# shield1.net
KiCad netlist of a schematic drawn in EAGLE
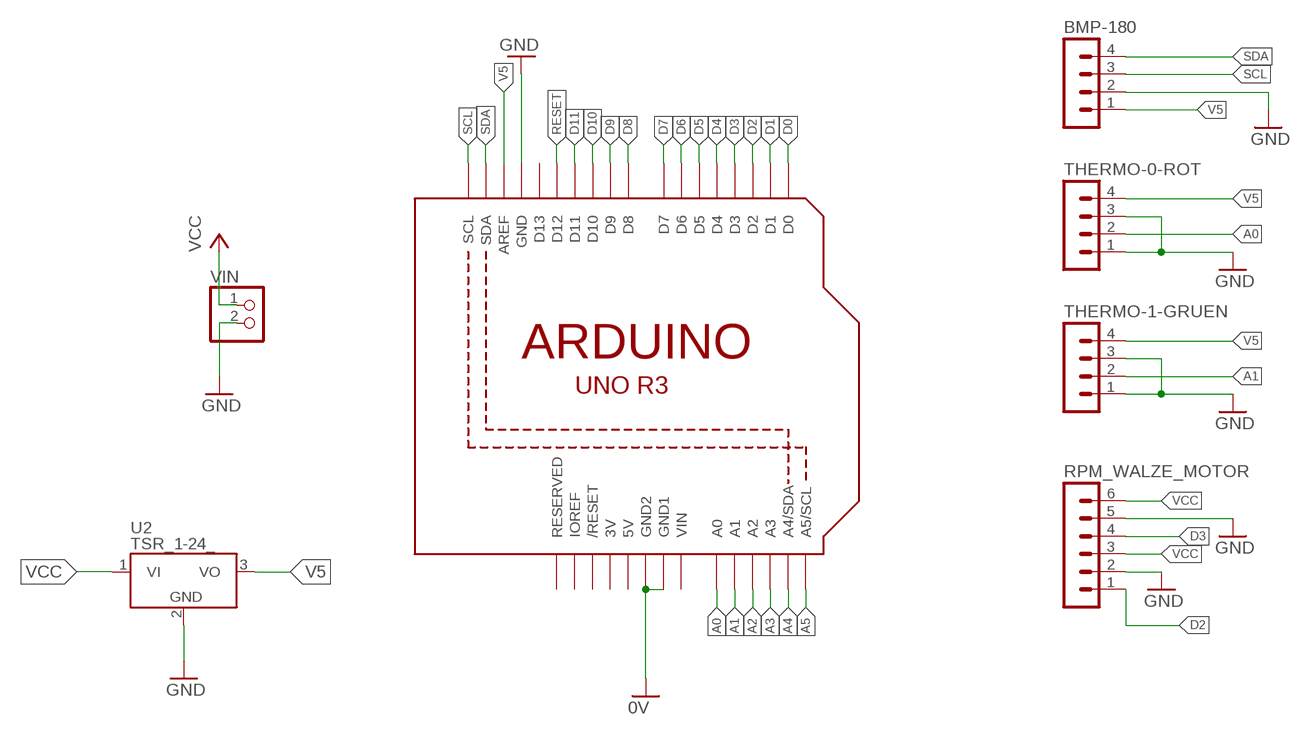
[diagram p0: schematic, sheet 1]

(export (version "E")
  (design (tool "Eeschema 10.0.6"))
  (components
    (comp (ref "BMP-180")
      (value "MA04-1")
      (footprint "eagle-import:MA04-1")
      (libsource (lib "eagle-import") (part "MA04-1"))
    )
    (comp (ref "RPM_WALZE_MOTOR")
      (value "MA06-1")
      (footprint "eagle-import:MA06-1")
      (libsource (lib "eagle-import") (part "MA06-1"))
    )
    (comp (ref "THERMO-0-ROT")
      (value "MA04-1")
      (footprint "eagle-import:MA04-1")
      (libsource (lib "eagle-import") (part "MA04-1"))
    )
    (comp (ref "THERMO-1-GRUEN")
      (value "MA04-1")
      (footprint "eagle-import:MA04-1")
      (libsource (lib "eagle-import") (part "MA04-1"))
    )
    (comp (ref "U1")
      (value "ARDUINOR3-BPLACE")
      (footprint "eagle-import:ARDUINOR3-BPLACE")
      (libsource (lib "eagle-import") (part "ARDUINOR3-BPLACE"))
    )
    (comp (ref "U2")
      (value "TSR_1-24_")
      (footprint "eagle-import:TSR-1")
      (libsource (lib "eagle-import") (part "TSR_1-24_"))
    )
    (comp (ref "VIN")
      (value "PINHD-1X2")
      (footprint "eagle-import:1X02")
      (libsource (lib "eagle-import") (part "PINHD-1X2"))
    )
  )
  (nets
    (net (code "1") (name "/3V") (class "Default")
      (node (ref "U1") (pin "3V") (pinfunction "3V_3V") (pintype "power_in"))
    )
    (net (code "2") (name "/5V") (class "Default")
      (node (ref "U1") (pin "5V") (pinfunction "5V_5V") (pintype "power_in"))
    )
    (net (code "3") (name "/VIN") (class "Default")
      (node (ref "U1") (pin "VIN") (pinfunction "VIN_VIN") (pintype "power_in"))
    )
    (net (code "4") (name "0V") (class "Default")
      (node (ref "BMP-180") (pin "2") (pinfunction "2_2") (pintype "passive"))
      (node (ref "RPM_WALZE_MOTOR") (pin "2") (pinfunction "2_2") (pintype "passive"))
      (node (ref "RPM_WALZE_MOTOR") (pin "5") (pinfunction "5_5") (pintype "passive"))
      (node (ref "THERMO-0-ROT") (pin "1") (pinfunction "1_1") (pintype "passive"))
      (node (ref "THERMO-0-ROT") (pin "3") (pinfunction "3_3") (pintype "passive"))
      (node (ref "THERMO-1-GRUEN") (pin "1") (pinfunction "1_1") (pintype "passive"))
      (node (ref "THERMO-1-GRUEN") (pin "3") (pinfunction "3_3") (pintype "passive"))
      (node (ref "U1") (pin "GND") (pinfunction "GND_GND") (pintype "power_in"))
      (node (ref "U1") (pin "GND1") (pinfunction "GND1_GND1") (pintype "power_in"))
      (node (ref "U1") (pin "GND2") (pinfunction "GND2_GND2") (pintype "power_in"))
      (node (ref "U2") (pin "2") (pinfunction "GND_2") (pintype "power_in"))
      (node (ref "VIN") (pin "2") (pinfunction "2_2") (pintype "passive"))
    )
    (net (code "5") (name "A0") (class "Default")
      (node (ref "THERMO-0-ROT") (pin "2") (pinfunction "2_2") (pintype "passive"))
      (node (ref "U1") (pin "A0") (pinfunction "A0_A0") (pintype "bidirectional"))
    )
    (net (code "6") (name "A1") (class "Default")
      (node (ref "THERMO-1-GRUEN") (pin "2") (pinfunction "2_2") (pintype "passive"))
      (node (ref "U1") (pin "A1") (pinfunction "A1_A1") (pintype "bidirectional"))
    )
    (net (code "7") (name "A2") (class "Default")
      (node (ref "U1") (pin "A2") (pinfunction "A2_A2") (pintype "bidirectional"))
    )
    (net (code "8") (name "A3") (class "Default")
      (node (ref "U1") (pin "A3") (pinfunction "A3_A3") (pintype "bidirectional"))
    )
    (net (code "9") (name "A4") (class "Default")
      (node (ref "U1") (pin "A4") (pinfunction "A4/SDA_A4") (pintype "bidirectional"))
    )
    (net (code "10") (name "A5") (class "Default")
      (node (ref "U1") (pin "A5") (pinfunction "A5/SCL_A5") (pintype "bidirectional"))
    )
    (net (code "11") (name "D0") (class "Default")
      (node (ref "U1") (pin "D0") (pinfunction "D0_D0") (pintype "bidirectional"))
    )
    (net (code "12") (name "D1") (class "Default")
      (node (ref "U1") (pin "D1") (pinfunction "D1_D1") (pintype "bidirectional"))
    )
    (net (code "13") (name "D2") (class "Default")
      (node (ref "RPM_WALZE_MOTOR") (pin "1") (pinfunction "1_1") (pintype "passive"))
      (node (ref "U1") (pin "D2") (pinfunction "D2_D2") (pintype "bidirectional"))
    )
    (net (code "14") (name "D3") (class "Default")
      (node (ref "RPM_WALZE_MOTOR") (pin "4") (pinfunction "4_4") (pintype "passive"))
      (node (ref "U1") (pin "D3") (pinfunction "D3_D3") (pintype "bidirectional"))
    )
    (net (code "15") (name "D4") (class "Default")
      (node (ref "U1") (pin "D4") (pinfunction "D4_D4") (pintype "bidirectional"))
    )
    (net (code "16") (name "D5") (class "Default")
      (node (ref "U1") (pin "D5") (pinfunction "D5_D5") (pintype "bidirectional"))
    )
    (net (code "17") (name "D6") (class "Default")
      (node (ref "U1") (pin "D6") (pinfunction "D6_D6") (pintype "bidirectional"))
    )
    (net (code "18") (name "D7") (class "Default")
      (node (ref "U1") (pin "D7") (pinfunction "D7_D7") (pintype "bidirectional"))
    )
    (net (code "19") (name "D8") (class "Default")
      (node (ref "U1") (pin "D8") (pinfunction "D8_D8") (pintype "bidirectional"))
    )
    (net (code "20") (name "D9") (class "Default")
      (node (ref "U1") (pin "D9") (pinfunction "D9_D9") (pintype "bidirectional"))
    )
    (net (code "21") (name "D10") (class "Default")
      (node (ref "U1") (pin "D10") (pinfunction "D10_D10") (pintype "bidirectional"))
    )
    (net (code "22") (name "D11") (class "Default")
      (node (ref "U1") (pin "D11") (pinfunction "D11_D11") (pintype "bidirectional"))
    )
    (net (code "23") (name "RESET") (class "Default")
      (node (ref "U1") (pin "D12") (pinfunction "D12_D12") (pintype "bidirectional"))
    )
    (net (code "24") (name "SCL") (class "Default")
      (node (ref "BMP-180") (pin "3") (pinfunction "3_3") (pintype "passive"))
      (node (ref "U1") (pin "SCL") (pinfunction "SCL_SCL") (pintype "bidirectional"))
    )
    (net (code "25") (name "SDA") (class "Default")
      (node (ref "BMP-180") (pin "4") (pinfunction "4_4") (pintype "passive"))
      (node (ref "U1") (pin "SDA") (pinfunction "SDA_SDA") (pintype "bidirectional"))
    )
    (net (code "26") (name "V5") (class "Default")
      (node (ref "BMP-180") (pin "1") (pinfunction "1_1") (pintype "passive"))
      (node (ref "THERMO-0-ROT") (pin "4") (pinfunction "4_4") (pintype "passive"))
      (node (ref "THERMO-1-GRUEN") (pin "4") (pinfunction "4_4") (pintype "passive"))
      (node (ref "U1") (pin "AREF") (pinfunction "AREF_AREF") (pintype "bidirectional"))
      (node (ref "U2") (pin "3") (pinfunction "VO_3") (pintype "power_in"))
    )
    (net (code "27") (name "VCC") (class "Default")
      (node (ref "RPM_WALZE_MOTOR") (pin "3") (pinfunction "3_3") (pintype "passive"))
      (node (ref "RPM_WALZE_MOTOR") (pin "6") (pinfunction "6_6") (pintype "passive"))
      (node (ref "U2") (pin "1") (pinfunction "VI_1") (pintype "power_in"))
      (node (ref "VIN") (pin "1") (pinfunction "1_1") (pintype "passive"))
    )
    (net (code "28") (name "unconnected-(U1-PadD13)") (class "Default")
      (node (ref "U1") (pin "D13") (pinfunction "D13_D13") (pintype "bidirectional"))
    )
    (net (code "29") (name "unconnected-(U1-PadIOREF)") (class "Default")
      (node (ref "U1") (pin "IOREF") (pinfunction "IOREF_IOREF") (pintype "output"))
    )
    (net (code "30") (name "unconnected-(U1-PadRESERVED)") (class "Default")
      (node (ref "U1") (pin "RESERVED") (pinfunction "RESERVED_RESERVED") (pintype "no_connect"))
    )
    (net (code "31") (name "unconnected-(U1-{slash}RESET-PadRESET)") (class "Default")
      (node (ref "U1") (pin "RESET") (pinfunction "/RESET_RESET") (pintype "bidirectional"))
    )
  )
)
